# UI.net
KiCad netlist of a schematic drawn in Altium Designer
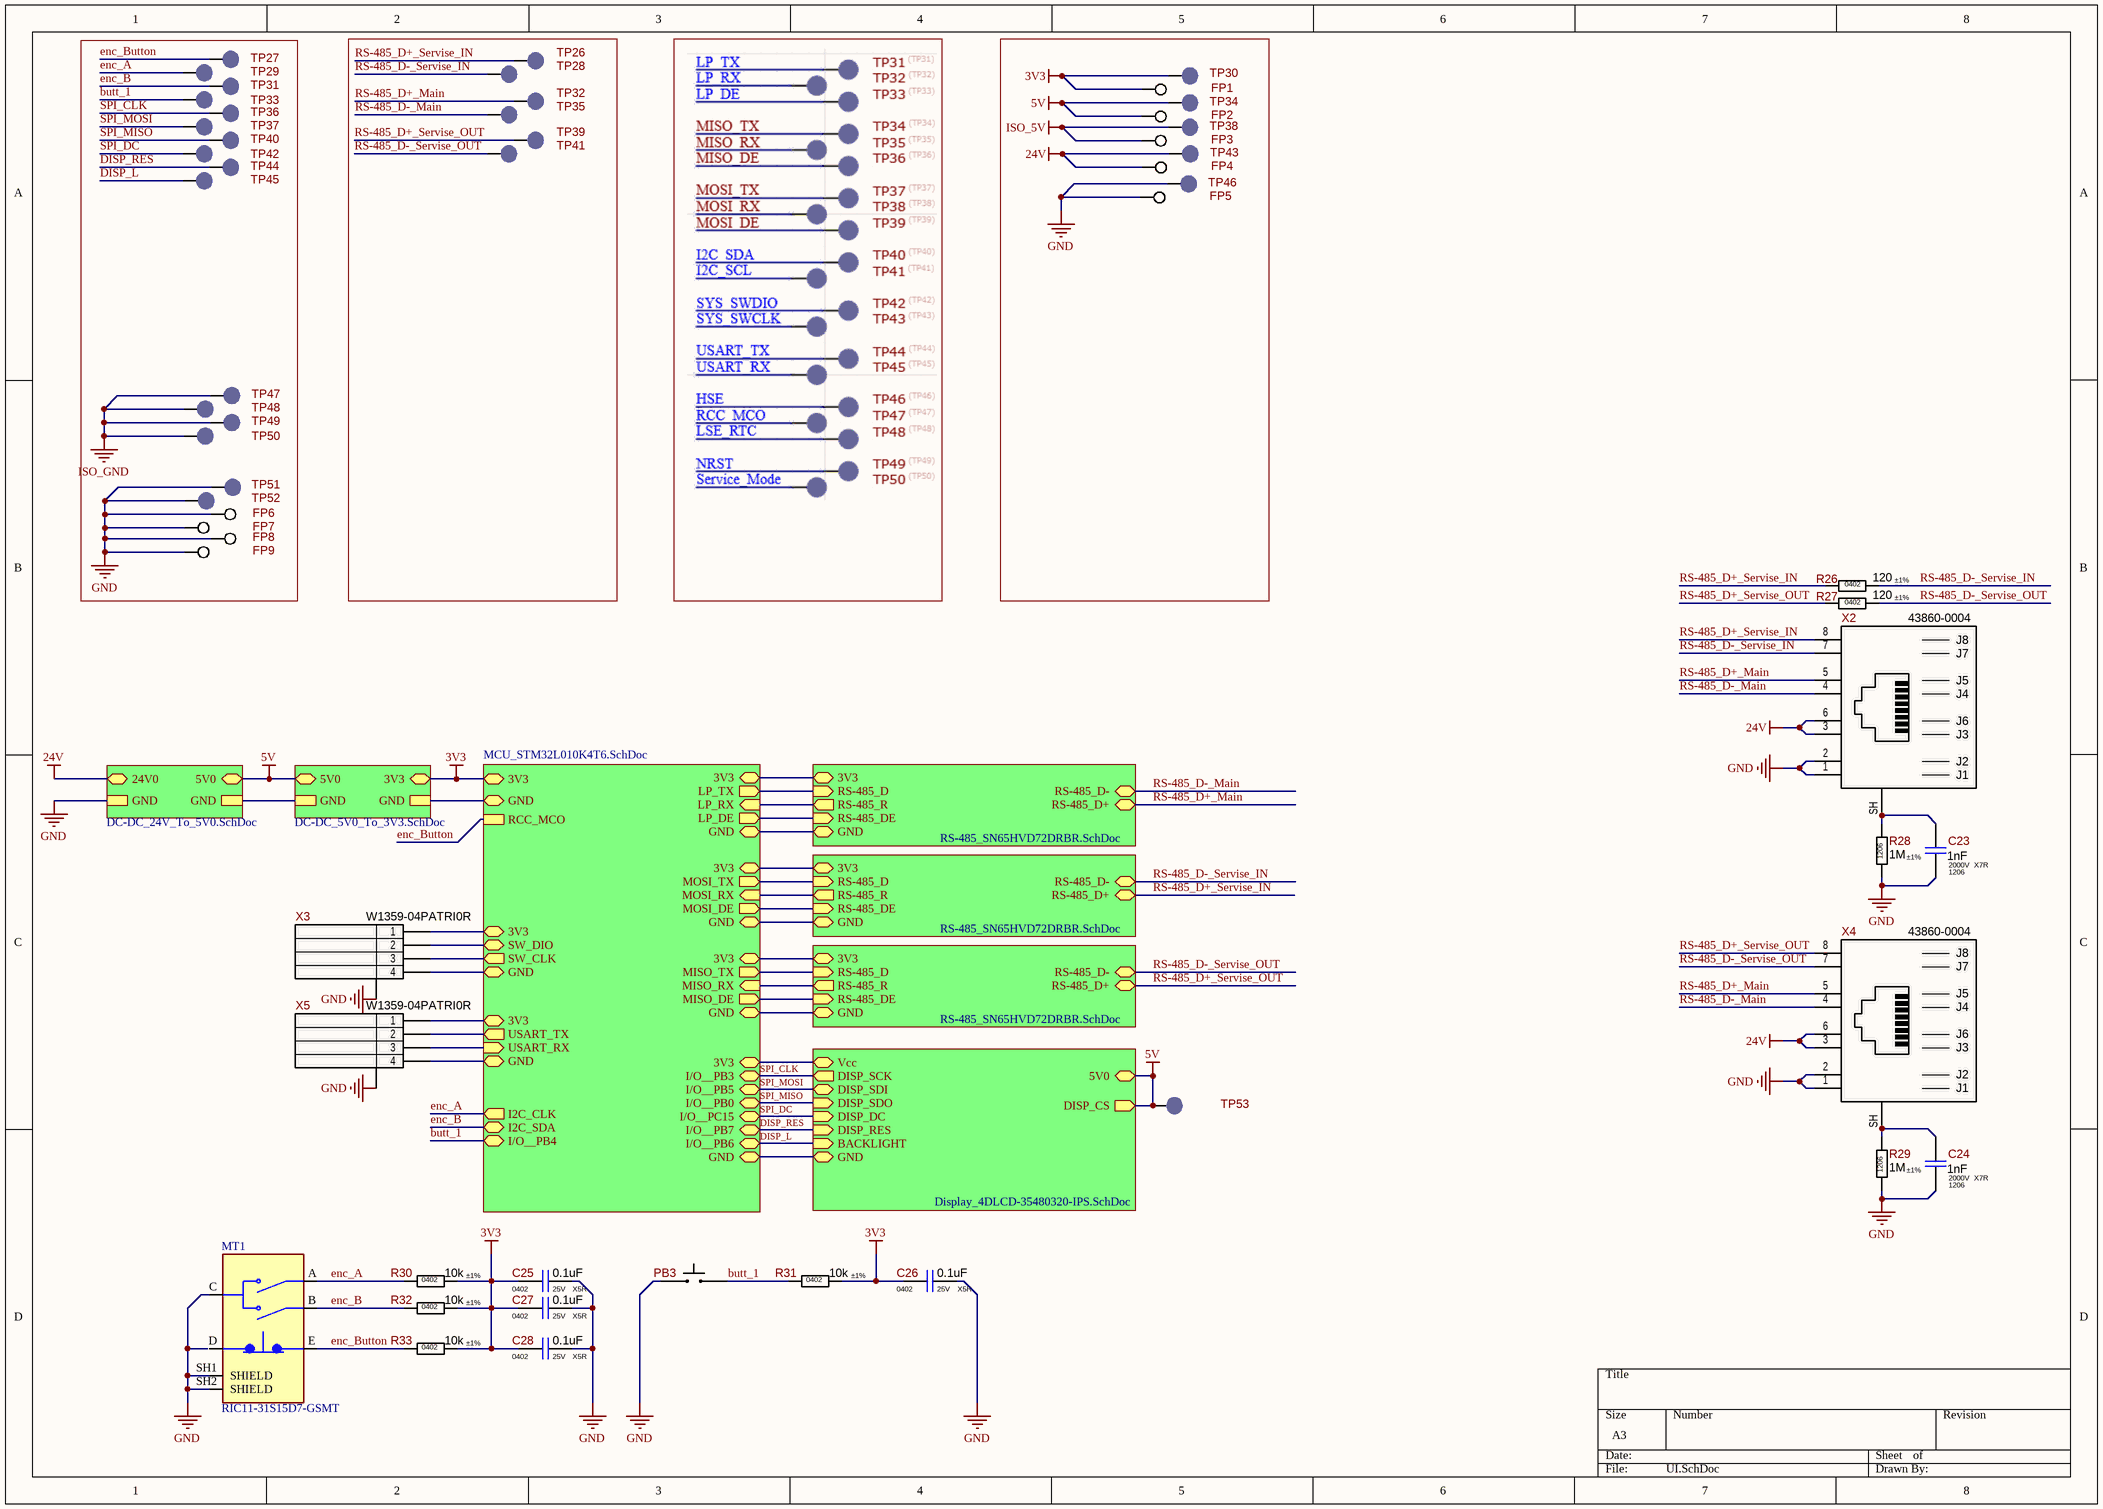
[diagram p0: UI.SchDoc]

(export (version "E")
  (design (tool "Eeschema 10.0.6"))
  (components
    (comp (ref "C23")
      (value "1nF")
      (footprint "CAP-1206(3216)X125T20")
      (description "1nF 2000V X7R ±10% 1206 Ceramic Capacitor RoHS")
      (fields
        (field (name "PACKAGE") "1206")
        (field (name "VOLTAGE") "2000V")
        (field (name "DIELECTRIC TYPE") "X7R")
        (field (name "PART NUMBER") "CC1206KKX7RDBB102")
        (field (name "MANUFACTURER") "Yageo")
      )
      (libsource (lib "EL.XXX.T01") (part "Capacitor-NonPolar"))
    )
    (comp (ref "C24")
      (value "1nF")
      (footprint "CAP-1206(3216)X125T20")
      (description "1nF 2000V X7R ±10% 1206 Ceramic Capacitor RoHS")
      (fields
        (field (name "PACKAGE") "1206")
        (field (name "VOLTAGE") "2000V")
        (field (name "DIELECTRIC TYPE") "X7R")
        (field (name "PART NUMBER") "CC1206KKX7RDBB102")
        (field (name "MANUFACTURER") "Yageo")
      )
      (libsource (lib "EL.XXX.T01") (part "Capacitor-NonPolar"))
    )
    (comp (ref "C25")
      (value "0.1uF")
      (footprint "C_CERAMIC_0402_HI")
      (description "100nF 25V X5R ±10% 0402 Ceramic Capacitor RoHS")
      (fields
        (field (name "PACKAGE") "0402")
        (field (name "VOLTAGE") "25V")
        (field (name "DIELECTRIC TYPE") "X5R")
        (field (name "PART NUMBER") "CL05A104KA5NNNC")
        (field (name "MANUFACTURER") "Samsung Electro-Mechanics")
      )
      (libsource (lib "EL.XXX.T01") (part "CL05A104KA5NNNC"))
    )
    (comp (ref "C26")
      (value "0.1uF")
      (footprint "C_CERAMIC_0402_HI")
      (description "100nF 25V X5R ±10% 0402 Ceramic Capacitor RoHS")
      (fields
        (field (name "PACKAGE") "0402")
        (field (name "VOLTAGE") "25V")
        (field (name "DIELECTRIC TYPE") "X5R")
        (field (name "PART NUMBER") "CL05A104KA5NNNC")
        (field (name "MANUFACTURER") "Samsung Electro-Mechanics")
      )
      (libsource (lib "EL.XXX.T01") (part "CL05A104KA5NNNC"))
    )
    (comp (ref "C27")
      (value "0.1uF")
      (footprint "C_CERAMIC_0402_HI")
      (description "100nF 25V X5R ±10% 0402 Ceramic Capacitor RoHS")
      (fields
        (field (name "PACKAGE") "0402")
        (field (name "VOLTAGE") "25V")
        (field (name "DIELECTRIC TYPE") "X5R")
        (field (name "PART NUMBER") "CL05A104KA5NNNC")
        (field (name "MANUFACTURER") "Samsung Electro-Mechanics")
      )
      (libsource (lib "EL.XXX.T01") (part "CL05A104KA5NNNC"))
    )
    (comp (ref "C28")
      (value "0.1uF")
      (footprint "C_CERAMIC_0402_HI")
      (description "100nF 25V X5R ±10% 0402 Ceramic Capacitor RoHS")
      (fields
        (field (name "PACKAGE") "0402")
        (field (name "VOLTAGE") "25V")
        (field (name "DIELECTRIC TYPE") "X5R")
        (field (name "PART NUMBER") "CL05A104KA5NNNC")
        (field (name "MANUFACTURER") "Samsung Electro-Mechanics")
      )
      (libsource (lib "EL.XXX.T01") (part "CL05A104KA5NNNC"))
    )
    (comp (ref "FP1")
      (value "PAD-1.1mm")
      (footprint "PAD-1.1mm")
      (description "1.1mm Pad for Plug-In or Receptacle")
      (fields (field (name "MANUFACTURER") "NONE"))
      (libsource (lib "EL.XXX.T01") (part "Pad"))
    )
    (comp (ref "FP2")
      (value "PAD-1.1mm")
      (footprint "PAD-1.1mm")
      (description "1.1mm Pad for Plug-In or Receptacle")
      (fields (field (name "MANUFACTURER") "NONE"))
      (libsource (lib "EL.XXX.T01") (part "Pad"))
    )
    (comp (ref "FP3")
      (value "PAD-1.1mm")
      (footprint "PAD-1.1mm")
      (description "1.1mm Pad for Plug-In or Receptacle")
      (fields (field (name "MANUFACTURER") "NONE"))
      (libsource (lib "EL.XXX.T01") (part "Pad"))
    )
    (comp (ref "FP4")
      (value "PAD-1.1mm")
      (footprint "PAD-1.1mm")
      (description "1.1mm Pad for Plug-In or Receptacle")
      (fields (field (name "MANUFACTURER") "NONE"))
      (libsource (lib "EL.XXX.T01") (part "Pad"))
    )
    (comp (ref "FP5")
      (value "PAD-1.1mm")
      (footprint "PAD-1.1mm")
      (description "1.1mm Pad for Plug-In or Receptacle")
      (fields (field (name "MANUFACTURER") "NONE"))
      (libsource (lib "EL.XXX.T01") (part "Pad"))
    )
    (comp (ref "FP6")
      (value "PAD-1.1mm")
      (footprint "PAD-1.1mm")
      (description "1.1mm Pad for Plug-In or Receptacle")
      (fields (field (name "MANUFACTURER") "NONE"))
      (libsource (lib "EL.XXX.T01") (part "Pad"))
    )
    (comp (ref "FP7")
      (value "PAD-1.1mm")
      (footprint "PAD-1.1mm")
      (description "1.1mm Pad for Plug-In or Receptacle")
      (fields (field (name "MANUFACTURER") "NONE"))
      (libsource (lib "EL.XXX.T01") (part "Pad"))
    )
    (comp (ref "FP8")
      (value "PAD-1.1mm")
      (footprint "PAD-1.1mm")
      (description "1.1mm Pad for Plug-In or Receptacle")
      (fields (field (name "MANUFACTURER") "NONE"))
      (libsource (lib "EL.XXX.T01") (part "Pad"))
    )
    (comp (ref "FP9")
      (value "PAD-1.1mm")
      (footprint "PAD-1.1mm")
      (description "1.1mm Pad for Plug-In or Receptacle")
      (fields (field (name "MANUFACTURER") "NONE"))
      (libsource (lib "EL.XXX.T01") (part "Pad"))
    )
    (comp (ref "MT1")
      (value "RIC11-31S15D7-GSMT")
      (footprint "XDCR_RIC11-31S15D7-GSMT")
      (description "Encoders MECH, 15 PPR 30 DET, 5 Vdc, SW, 7 mm smth bush, D shaft, horizontal, GSMT")
      (libsource (lib "EL.XXX.T01") (part "RIC11-31S15D7-GSMT"))
    )
    (comp (ref "PB3")
      (value "DS1042-24-2017VBR16005")
      (footprint "DS1042-24-2017VB")
      (description "Tactile Switch 2.5x3mm, SMD, 160gf, Height 1.7mm, 50mA 12VDC")
      (fields (field (name "MANUFACTURER") "Connfly"))
      (libsource (lib "EL.XXX.T01") (part "DS1042-24-2017VBR16005"))
    )
    (comp (ref "R26")
      (value "120")
      (footprint "R_ANY_CHIP_0402_HI")
      (description "120 Ohms ±1% 1/16W 0402 Thick Film Resistor")
      (fields
        (field (name "TOLERANCE") "±1%")
        (field (name "PACKAGE") "0402")
        (field (name "PART NUMBER") "RC0402FR-07120RL")
        (field (name "MANUFACTURER") "Yageo")
      )
      (libsource (lib "EL.XXX.T01") (part "Resistor"))
    )
    (comp (ref "R27")
      (value "120")
      (footprint "R_ANY_CHIP_0402_HI")
      (description "120 Ohms ±1% 1/16W 0402 Thick Film Resistor")
      (fields
        (field (name "TOLERANCE") "±1%")
        (field (name "PACKAGE") "0402")
        (field (name "PART NUMBER") "RC0402FR-07120RL")
        (field (name "MANUFACTURER") "Yageo")
      )
      (libsource (lib "EL.XXX.T01") (part "Resistor"))
    )
    (comp (ref "R28")
      (value "1M")
      (footprint "CHV1206-Series")
      (description "1 MOhms ±1%, 1/4W 1206 Thick Film Resistor")
      (fields
        (field (name "TOLERANCE") "±1%")
        (field (name "PACKAGE") "1206")
        (field (name "PART NUMBER") "CHV1206-FX-1004ELF")
        (field (name "MANUFACTURER") "Bourns")
      )
      (libsource (lib "EL.XXX.T01") (part "Resistor"))
    )
    (comp (ref "R29")
      (value "1M")
      (footprint "CHV1206-Series")
      (description "1 MOhms ±1%, 1/4W 1206 Thick Film Resistor")
      (fields
        (field (name "TOLERANCE") "±1%")
        (field (name "PACKAGE") "1206")
        (field (name "PART NUMBER") "CHV1206-FX-1004ELF")
        (field (name "MANUFACTURER") "Bourns")
      )
      (libsource (lib "EL.XXX.T01") (part "Resistor"))
    )
    (comp (ref "R30")
      (value "10k")
      (footprint "R_ANY_CHIP_0402_MED")
      (description "10 kOhms ±1% 1/16W 0402 Thick Film Resistor")
      (fields
        (field (name "TOLERANCE") "±1%")
        (field (name "PACKAGE") "0402")
        (field (name "PART NUMBER") "RC0402FR-0710KL")
        (field (name "MANUFACTURER") "Yageo")
      )
      (libsource (lib "EL.XXX.T01") (part "RC0402FR-0710KL"))
    )
    (comp (ref "R31")
      (value "10k")
      (footprint "R_ANY_CHIP_0402_MED")
      (description "10 kOhms ±1% 1/16W 0402 Thick Film Resistor")
      (fields
        (field (name "TOLERANCE") "±1%")
        (field (name "PACKAGE") "0402")
        (field (name "PART NUMBER") "RC0402FR-0710KL")
        (field (name "MANUFACTURER") "Yageo")
      )
      (libsource (lib "EL.XXX.T01") (part "RC0402FR-0710KL"))
    )
    (comp (ref "R32")
      (value "10k")
      (footprint "R_ANY_CHIP_0402_MED")
      (description "10 kOhms ±1% 1/16W 0402 Thick Film Resistor")
      (fields
        (field (name "TOLERANCE") "±1%")
        (field (name "PACKAGE") "0402")
        (field (name "PART NUMBER") "RC0402FR-0710KL")
        (field (name "MANUFACTURER") "Yageo")
      )
      (libsource (lib "EL.XXX.T01") (part "RC0402FR-0710KL"))
    )
    (comp (ref "R33")
      (value "10k")
      (footprint "R_ANY_CHIP_0402_MED")
      (description "10 kOhms ±1% 1/16W 0402 Thick Film Resistor")
      (fields
        (field (name "TOLERANCE") "±1%")
        (field (name "PACKAGE") "0402")
        (field (name "PART NUMBER") "RC0402FR-0710KL")
        (field (name "MANUFACTURER") "Yageo")
      )
      (libsource (lib "EL.XXX.T01") (part "RC0402FR-0710KL"))
    )
    (comp (ref "TP26")
      (value "LED_LINK")
      (footprint "TP_SMD_2mm")
      (description "Test Point SMD Pad 1.0mm/1.5mm/2mm")
      (fields (field (name "PART NUMBER") "TP-PAD-SMD"))
      (libsource (lib "EL.XXX.T01") (part "Test-Point-SMD-1"))
    )
    (comp (ref "TP27")
      (value "LED_LINK")
      (footprint "TP_SMD_2mm")
      (description "Test Point SMD Pad 1.0mm/1.5mm/2mm")
      (fields (field (name "PART NUMBER") "TP-PAD-SMD"))
      (libsource (lib "EL.XXX.T01") (part "Test-Point-SMD-1"))
    )
    (comp (ref "TP28")
      (value "LED_LINK")
      (footprint "TP_SMD_2mm")
      (description "Test Point SMD Pad 1.0mm/1.5mm/2mm")
      (fields (field (name "PART NUMBER") "TP-PAD-SMD"))
      (libsource (lib "EL.XXX.T01") (part "Test-Point-SMD-1"))
    )
    (comp (ref "TP29")
      (value "LED_LINK")
      (footprint "TP_SMD_2mm")
      (description "Test Point SMD Pad 1.0mm/1.5mm/2mm")
      (fields (field (name "PART NUMBER") "TP-PAD-SMD"))
      (libsource (lib "EL.XXX.T01") (part "Test-Point-SMD-1"))
    )
    (comp (ref "TP30")
      (value "LED_LINK")
      (footprint "TP_SMD_2mm")
      (description "Test Point SMD Pad 1.0mm/1.5mm/2mm")
      (fields (field (name "PART NUMBER") "TP-PAD-SMD"))
      (libsource (lib "EL.XXX.T01") (part "Test-Point-SMD-1"))
    )
    (comp (ref "TP31")
      (value "LED_LINK")
      (footprint "TP_SMD_2mm")
      (description "Test Point SMD Pad 1.0mm/1.5mm/2mm")
      (fields (field (name "PART NUMBER") "TP-PAD-SMD"))
      (libsource (lib "EL.XXX.T01") (part "Test-Point-SMD-1"))
    )
    (comp (ref "TP32")
      (value "LED_LINK")
      (footprint "TP_SMD_2mm")
      (description "Test Point SMD Pad 1.0mm/1.5mm/2mm")
      (fields (field (name "PART NUMBER") "TP-PAD-SMD"))
      (libsource (lib "EL.XXX.T01") (part "Test-Point-SMD-1"))
    )
    (comp (ref "TP33")
      (value "LED_LINK")
      (footprint "TP_SMD_2mm")
      (description "Test Point SMD Pad 1.0mm/1.5mm/2mm")
      (fields (field (name "PART NUMBER") "TP-PAD-SMD"))
      (libsource (lib "EL.XXX.T01") (part "Test-Point-SMD-1"))
    )
    (comp (ref "TP34")
      (value "LED_LINK")
      (footprint "TP_SMD_2mm")
      (description "Test Point SMD Pad 1.0mm/1.5mm/2mm")
      (fields (field (name "PART NUMBER") "TP-PAD-SMD"))
      (libsource (lib "EL.XXX.T01") (part "Test-Point-SMD-1"))
    )
    (comp (ref "TP35")
      (value "LED_LINK")
      (footprint "TP_SMD_2mm")
      (description "Test Point SMD Pad 1.0mm/1.5mm/2mm")
      (fields (field (name "PART NUMBER") "TP-PAD-SMD"))
      (libsource (lib "EL.XXX.T01") (part "Test-Point-SMD-1"))
    )
    (comp (ref "TP36")
      (value "LED_LINK")
      (footprint "TP_SMD_2mm")
      (description "Test Point SMD Pad 1.0mm/1.5mm/2mm")
      (fields (field (name "PART NUMBER") "TP-PAD-SMD"))
      (libsource (lib "EL.XXX.T01") (part "Test-Point-SMD-1"))
    )
    (comp (ref "TP37")
      (value "LED_LINK")
      (footprint "TP_SMD_2mm")
      (description "Test Point SMD Pad 1.0mm/1.5mm/2mm")
      (fields (field (name "PART NUMBER") "TP-PAD-SMD"))
      (libsource (lib "EL.XXX.T01") (part "Test-Point-SMD-1"))
    )
    (comp (ref "TP38")
      (value "LED_LINK")
      (footprint "TP_SMD_2mm")
      (description "Test Point SMD Pad 1.0mm/1.5mm/2mm")
      (fields (field (name "PART NUMBER") "TP-PAD-SMD"))
      (libsource (lib "EL.XXX.T01") (part "Test-Point-SMD-1"))
    )
    (comp (ref "TP39")
      (value "LED_LINK")
      (footprint "TP_SMD_2mm")
      (description "Test Point SMD Pad 1.0mm/1.5mm/2mm")
      (fields (field (name "PART NUMBER") "TP-PAD-SMD"))
      (libsource (lib "EL.XXX.T01") (part "Test-Point-SMD-1"))
    )
    (comp (ref "TP40")
      (value "LED_LINK")
      (footprint "TP_SMD_2mm")
      (description "Test Point SMD Pad 1.0mm/1.5mm/2mm")
      (fields (field (name "PART NUMBER") "TP-PAD-SMD"))
      (libsource (lib "EL.XXX.T01") (part "Test-Point-SMD-1"))
    )
    (comp (ref "TP41")
      (value "LED_LINK")
      (footprint "TP_SMD_2mm")
      (description "Test Point SMD Pad 1.0mm/1.5mm/2mm")
      (fields (field (name "PART NUMBER") "TP-PAD-SMD"))
      (libsource (lib "EL.XXX.T01") (part "Test-Point-SMD-1"))
    )
    (comp (ref "TP42")
      (value "LED_LINK")
      (footprint "TP_SMD_2mm")
      (description "Test Point SMD Pad 1.0mm/1.5mm/2mm")
      (fields (field (name "PART NUMBER") "TP-PAD-SMD"))
      (libsource (lib "EL.XXX.T01") (part "Test-Point-SMD-1"))
    )
    (comp (ref "TP43")
      (value "LED_LINK")
      (footprint "TP_SMD_2mm")
      (description "Test Point SMD Pad 1.0mm/1.5mm/2mm")
      (fields (field (name "PART NUMBER") "TP-PAD-SMD"))
      (libsource (lib "EL.XXX.T01") (part "Test-Point-SMD-1"))
    )
    (comp (ref "TP44")
      (value "LED_LINK")
      (footprint "TP_SMD_2mm")
      (description "Test Point SMD Pad 1.0mm/1.5mm/2mm")
      (fields (field (name "PART NUMBER") "TP-PAD-SMD"))
      (libsource (lib "EL.XXX.T01") (part "Test-Point-SMD-1"))
    )
    (comp (ref "TP45")
      (value "LED_LINK")
      (footprint "TP_SMD_2mm")
      (description "Test Point SMD Pad 1.0mm/1.5mm/2mm")
      (fields (field (name "PART NUMBER") "TP-PAD-SMD"))
      (libsource (lib "EL.XXX.T01") (part "Test-Point-SMD-1"))
    )
    (comp (ref "TP46")
      (value "LED_LINK")
      (footprint "TP_SMD_2mm")
      (description "Test Point SMD Pad 1.0mm/1.5mm/2mm")
      (fields (field (name "PART NUMBER") "TP-PAD-SMD"))
      (libsource (lib "EL.XXX.T01") (part "Test-Point-SMD-1"))
    )
    (comp (ref "TP47")
      (value "LED_LINK")
      (footprint "TP_SMD_2mm")
      (description "Test Point SMD Pad 1.0mm/1.5mm/2mm")
      (fields (field (name "PART NUMBER") "TP-PAD-SMD"))
      (libsource (lib "EL.XXX.T01") (part "Test-Point-SMD-1"))
    )
    (comp (ref "TP48")
      (value "LED_LINK")
      (footprint "TP_SMD_2mm")
      (description "Test Point SMD Pad 1.0mm/1.5mm/2mm")
      (fields (field (name "PART NUMBER") "TP-PAD-SMD"))
      (libsource (lib "EL.XXX.T01") (part "Test-Point-SMD-1"))
    )
    (comp (ref "TP49")
      (value "LED_LINK")
      (footprint "TP_SMD_2mm")
      (description "Test Point SMD Pad 1.0mm/1.5mm/2mm")
      (fields (field (name "PART NUMBER") "TP-PAD-SMD"))
      (libsource (lib "EL.XXX.T01") (part "Test-Point-SMD-1"))
    )
    (comp (ref "TP50")
      (value "LED_LINK")
      (footprint "TP_SMD_2mm")
      (description "Test Point SMD Pad 1.0mm/1.5mm/2mm")
      (fields (field (name "PART NUMBER") "TP-PAD-SMD"))
      (libsource (lib "EL.XXX.T01") (part "Test-Point-SMD-1"))
    )
    (comp (ref "TP51")
      (value "LED_LINK")
      (footprint "TP_SMD_2mm")
      (description "Test Point SMD Pad 1.0mm/1.5mm/2mm")
      (fields (field (name "PART NUMBER") "TP-PAD-SMD"))
      (libsource (lib "EL.XXX.T01") (part "Test-Point-SMD-1"))
    )
    (comp (ref "TP52")
      (value "LED_LINK")
      (footprint "TP_SMD_2mm")
      (description "Test Point SMD Pad 1.0mm/1.5mm/2mm")
      (fields (field (name "PART NUMBER") "TP-PAD-SMD"))
      (libsource (lib "EL.XXX.T01") (part "Test-Point-SMD-1"))
    )
    (comp (ref "TP53")
      (value "LED_LINK")
      (footprint "TP_SMD_2mm")
      (description "Test Point SMD Pad 1.0mm/1.5mm/2mm")
      (fields (field (name "PART NUMBER") "TP-PAD-SMD"))
      (libsource (lib "EL.XXX.T01") (part "Test-Point-SMD-1"))
    )
    (comp (ref "X2")
      (value "43860-0004")
      (footprint "43860-0004")
      (description "RJ45 8P8C Shielded Cat 3 10 Base-T Connector")
      (fields (field (name "PART NUMBER") "43860-0004") (field (name "MANUFACTURER") "Molex"))
      (libsource (lib "EL.XXX.T01") (part "43860-0004"))
    )
    (comp (ref "X3")
      (value "W1359-04PATRI0R")
      (footprint "W1359-04PATXI0R_DBG")
      (description "1.25mm Wire-to-Board Header, Vertical, SMT, 4 pin")
      (fields
        (field (name "PART NUMBER") "W1359-04PATRI0R")
        (field (name "MANUFACTURER") "Hsuan Mao Technology")
      )
      (libsource (lib "EL.XXX.T01") (part "General-4-Pin-MP"))
    )
    (comp (ref "X4")
      (value "43860-0004")
      (footprint "43860-0004")
      (description "RJ45 8P8C Shielded Cat 3 10 Base-T Connector")
      (fields (field (name "PART NUMBER") "43860-0004") (field (name "MANUFACTURER") "Molex"))
      (libsource (lib "EL.XXX.T01") (part "43860-0004"))
    )
    (comp (ref "X5")
      (value "W1359-04PATRI0R")
      (footprint "W1359-04PATXI0R_DBG")
      (description "1.25mm Wire-to-Board Header, Vertical, SMT, 4 pin")
      (fields
        (field (name "PART NUMBER") "W1359-04PATRI0R")
        (field (name "MANUFACTURER") "Hsuan Mao Technology")
      )
      (libsource (lib "EL.XXX.T01") (part "General-4-Pin-MP"))
    )
  )
  (nets
    (net (code "3") (name "/3V3_2") (class "Default")
      (node (ref "X3") (pin "1") (pinfunction "1_1") (pintype "passive"))
    )
    (net (code "5") (name "/3V3_4") (class "Default")
      (node (ref "X5") (pin "1") (pinfunction "1_1") (pintype "passive"))
    )
    (net (code "10") (name "/DISP_L") (class "Default") (node (ref "TP45") (pin "1") (pintype "passive")))
    (net (code "11") (name "/DISP_RES") (class "Default") (node (ref "TP44") (pin "1") (pintype "passive")))
    (net (code "13") (name "/GND_1") (class "Default")
      (node (ref "X5") (pin "4") (pinfunction "4_4") (pintype "passive"))
    )
    (net (code "19") (name "/GND_7") (class "Default")
      (node (ref "X3") (pin "4") (pinfunction "4_4") (pintype "passive"))
    )
    (net (code "33") (name "/RS-485_D+_Main") (class "Default")
      (node (ref "TP32") (pin "1") (pintype "passive"))
      (node (ref "X2") (pin "5") (pinfunction "CT_5") (pintype "passive"))
      (node (ref "X4") (pin "5") (pinfunction "CT_5") (pintype "passive"))
    )
    (net (code "34") (name "/RS-485_D+_Servise_IN") (class "Default")
      (node (ref "R26") (pin "1") (pintype "passive"))
      (node (ref "TP26") (pin "1") (pintype "passive"))
      (node (ref "X2") (pin "8") (pinfunction "TD2+_8") (pintype "passive"))
    )
    (net (code "35") (name "/RS-485_D+_Servise_OUT") (class "Default")
      (node (ref "R27") (pin "1") (pintype "passive"))
      (node (ref "TP39") (pin "1") (pintype "passive"))
      (node (ref "X4") (pin "8") (pinfunction "TD2+_8") (pintype "passive"))
    )
    (net (code "36") (name "/RS-485_D-_Main") (class "Default")
      (node (ref "TP35") (pin "1") (pintype "passive"))
      (node (ref "X2") (pin "4") (pinfunction "TD3+_4") (pintype "passive"))
      (node (ref "X4") (pin "4") (pinfunction "TD3+_4") (pintype "passive"))
    )
    (net (code "37") (name "/RS-485_D-_Servise_IN") (class "Default")
      (node (ref "R26") (pin "2") (pintype "passive"))
      (node (ref "TP28") (pin "1") (pintype "passive"))
      (node (ref "X2") (pin "7") (pinfunction "TD2-_7") (pintype "passive"))
    )
    (net (code "38") (name "/RS-485_D-_Servise_OUT") (class "Default")
      (node (ref "R27") (pin "2") (pintype "passive"))
      (node (ref "TP41") (pin "1") (pintype "passive"))
      (node (ref "X4") (pin "7") (pinfunction "TD2-_7") (pintype "passive"))
    )
    (net (code "47") (name "/SPI_CLK") (class "Default") (node (ref "TP36") (pin "1") (pintype "passive")))
    (net (code "48") (name "/SPI_DC") (class "Default") (node (ref "TP42") (pin "1") (pintype "passive")))
    (net (code "49") (name "/SPI_MISO") (class "Default") (node (ref "TP40") (pin "1") (pintype "passive")))
    (net (code "50") (name "/SPI_MOSI") (class "Default") (node (ref "TP37") (pin "1") (pintype "passive")))
    (net (code "51") (name "/SW_CLK") (class "Default")
      (node (ref "X3") (pin "3") (pinfunction "3_3") (pintype "passive"))
    )
    (net (code "52") (name "/SW_DIO") (class "Default")
      (node (ref "X3") (pin "2") (pinfunction "2_2") (pintype "passive"))
    )
    (net (code "53") (name "/USART_RX") (class "Default")
      (node (ref "X5") (pin "3") (pinfunction "3_3") (pintype "passive"))
    )
    (net (code "54") (name "/USART_TX") (class "Default")
      (node (ref "X5") (pin "2") (pinfunction "2_2") (pintype "passive"))
    )
    (net (code "55") (name "/butt_1") (class "Default")
      (node (ref "PB3") (pin "2") (pintype "passive"))
      (node (ref "R31") (pin "2") (pintype "passive"))
      (node (ref "TP33") (pin "1") (pintype "passive"))
    )
    (net (code "56") (name "/enc_A") (class "Default")
      (node (ref "MT1") (pin "A") (pinfunction "A_A") (pintype "passive"))
      (node (ref "R30") (pin "2") (pintype "passive"))
      (node (ref "TP29") (pin "1") (pintype "passive"))
    )
    (net (code "57") (name "/enc_B") (class "Default")
      (node (ref "MT1") (pin "B") (pinfunction "B_B") (pintype "passive"))
      (node (ref "R32") (pin "2") (pintype "passive"))
      (node (ref "TP31") (pin "1") (pintype "passive"))
    )
    (net (code "58") (name "/enc_Button") (class "Default")
      (node (ref "MT1") (pin "E") (pinfunction "S2_E") (pintype "passive"))
      (node (ref "R33") (pin "2") (pintype "passive"))
      (node (ref "TP27") (pin "1") (pintype "passive"))
    )
    (net (code "59") (name "3V3") (class "Default")
      (node (ref "C25") (pin "1") (pinfunction "1_1") (pintype "passive"))
      (node (ref "C26") (pin "1") (pinfunction "1_1") (pintype "passive"))
      (node (ref "C27") (pin "1") (pinfunction "1_1") (pintype "passive"))
      (node (ref "C28") (pin "1") (pinfunction "1_1") (pintype "passive"))
      (node (ref "FP1") (pin "1") (pintype "passive"))
      (node (ref "R30") (pin "1") (pintype "passive"))
      (node (ref "R31") (pin "1") (pintype "passive"))
      (node (ref "R32") (pin "1") (pintype "passive"))
      (node (ref "R33") (pin "1") (pintype "passive"))
      (node (ref "TP30") (pin "1") (pintype "passive"))
    )
    (net (code "60") (name "5V") (class "Default")
      (node (ref "FP2") (pin "1") (pintype "passive"))
      (node (ref "TP34") (pin "1") (pintype "passive"))
      (node (ref "TP53") (pin "1") (pintype "passive"))
    )
    (net (code "61") (name "24V") (class "Default")
      (node (ref "FP4") (pin "1") (pintype "passive"))
      (node (ref "TP43") (pin "1") (pintype "passive"))
      (node (ref "X2") (pin "3") (pinfunction "TD3-_3") (pintype "passive"))
      (node (ref "X2") (pin "6") (pinfunction "CT_6") (pintype "passive"))
      (node (ref "X4") (pin "3") (pinfunction "TD3-_3") (pintype "passive"))
      (node (ref "X4") (pin "6") (pinfunction "CT_6") (pintype "passive"))
    )
    (net (code "62") (name "GND") (class "Default")
      (node (ref "C23") (pin "2") (pinfunction "2_2") (pintype "passive"))
      (node (ref "C24") (pin "2") (pinfunction "2_2") (pintype "passive"))
      (node (ref "C25") (pin "2") (pinfunction "2_2") (pintype "passive"))
      (node (ref "C26") (pin "2") (pinfunction "2_2") (pintype "passive"))
      (node (ref "C27") (pin "2") (pinfunction "2_2") (pintype "passive"))
      (node (ref "C28") (pin "2") (pinfunction "2_2") (pintype "passive"))
      (node (ref "FP5") (pin "1") (pintype "passive"))
      (node (ref "FP6") (pin "1") (pintype "passive"))
      (node (ref "FP7") (pin "1") (pintype "passive"))
      (node (ref "FP8") (pin "1") (pintype "passive"))
      (node (ref "FP9") (pin "1") (pintype "passive"))
      (node (ref "MT1") (pin "C") (pinfunction "C_C") (pintype "passive"))
      (node (ref "MT1") (pin "SH1") (pinfunction "SHIELD_SH1") (pintype "passive"))
      (node (ref "MT1") (pin "SH2") (pinfunction "SHIELD_SH2") (pintype "passive"))
      (node (ref "PB3") (pin "1") (pintype "passive"))
      (node (ref "R28") (pin "2") (pintype "passive"))
      (node (ref "R29") (pin "2") (pintype "passive"))
      (node (ref "TP46") (pin "1") (pintype "passive"))
      (node (ref "TP51") (pin "1") (pintype "passive"))
      (node (ref "TP52") (pin "1") (pintype "passive"))
      (node (ref "X2") (pin "1") (pinfunction "TD4-_1") (pintype "passive"))
      (node (ref "X2") (pin "2") (pinfunction "TD4+_2") (pintype "passive"))
      (node (ref "X3") (pin "MP") (pinfunction "MountPad_MP") (pintype "passive"))
      (node (ref "X4") (pin "1") (pinfunction "TD4-_1") (pintype "passive"))
      (node (ref "X4") (pin "2") (pinfunction "TD4+_2") (pintype "passive"))
      (node (ref "X5") (pin "MP") (pinfunction "MountPad_MP") (pintype "passive"))
    )
    (net (code "63") (name "ISO_5V") (class "Default")
      (node (ref "FP3") (pin "1") (pintype "passive"))
      (node (ref "TP38") (pin "1") (pintype "passive"))
    )
    (net (code "64") (name "ISO_GND") (class "Default")
      (node (ref "TP47") (pin "1") (pintype "passive"))
      (node (ref "TP48") (pin "1") (pintype "passive"))
      (node (ref "TP49") (pin "1") (pintype "passive"))
      (node (ref "TP50") (pin "1") (pintype "passive"))
    )
    (net (code "65") (name "Net-(X2-Shield)") (class "Default")
      (node (ref "C23") (pin "1") (pinfunction "1_1") (pintype "passive"))
      (node (ref "R28") (pin "1") (pintype "passive"))
      (node (ref "X2") (pin "SH") (pinfunction "Shield_SH") (pintype "passive"))
    )
    (net (code "66") (name "Net-(X4-Shield)") (class "Default")
      (node (ref "C24") (pin "1") (pinfunction "1_1") (pintype "passive"))
      (node (ref "R29") (pin "1") (pintype "passive"))
      (node (ref "X4") (pin "SH") (pinfunction "Shield_SH") (pintype "passive"))
    )
    (net (code "67") (name "unconnected-(MT1-S1-PadD)") (class "Default")
      (node (ref "MT1") (pin "D") (pinfunction "S1_D") (pintype "passive"))
    )
  )
)
